# SolarCharge.net
KiCad netlist of a schematic drawn in EAGLE
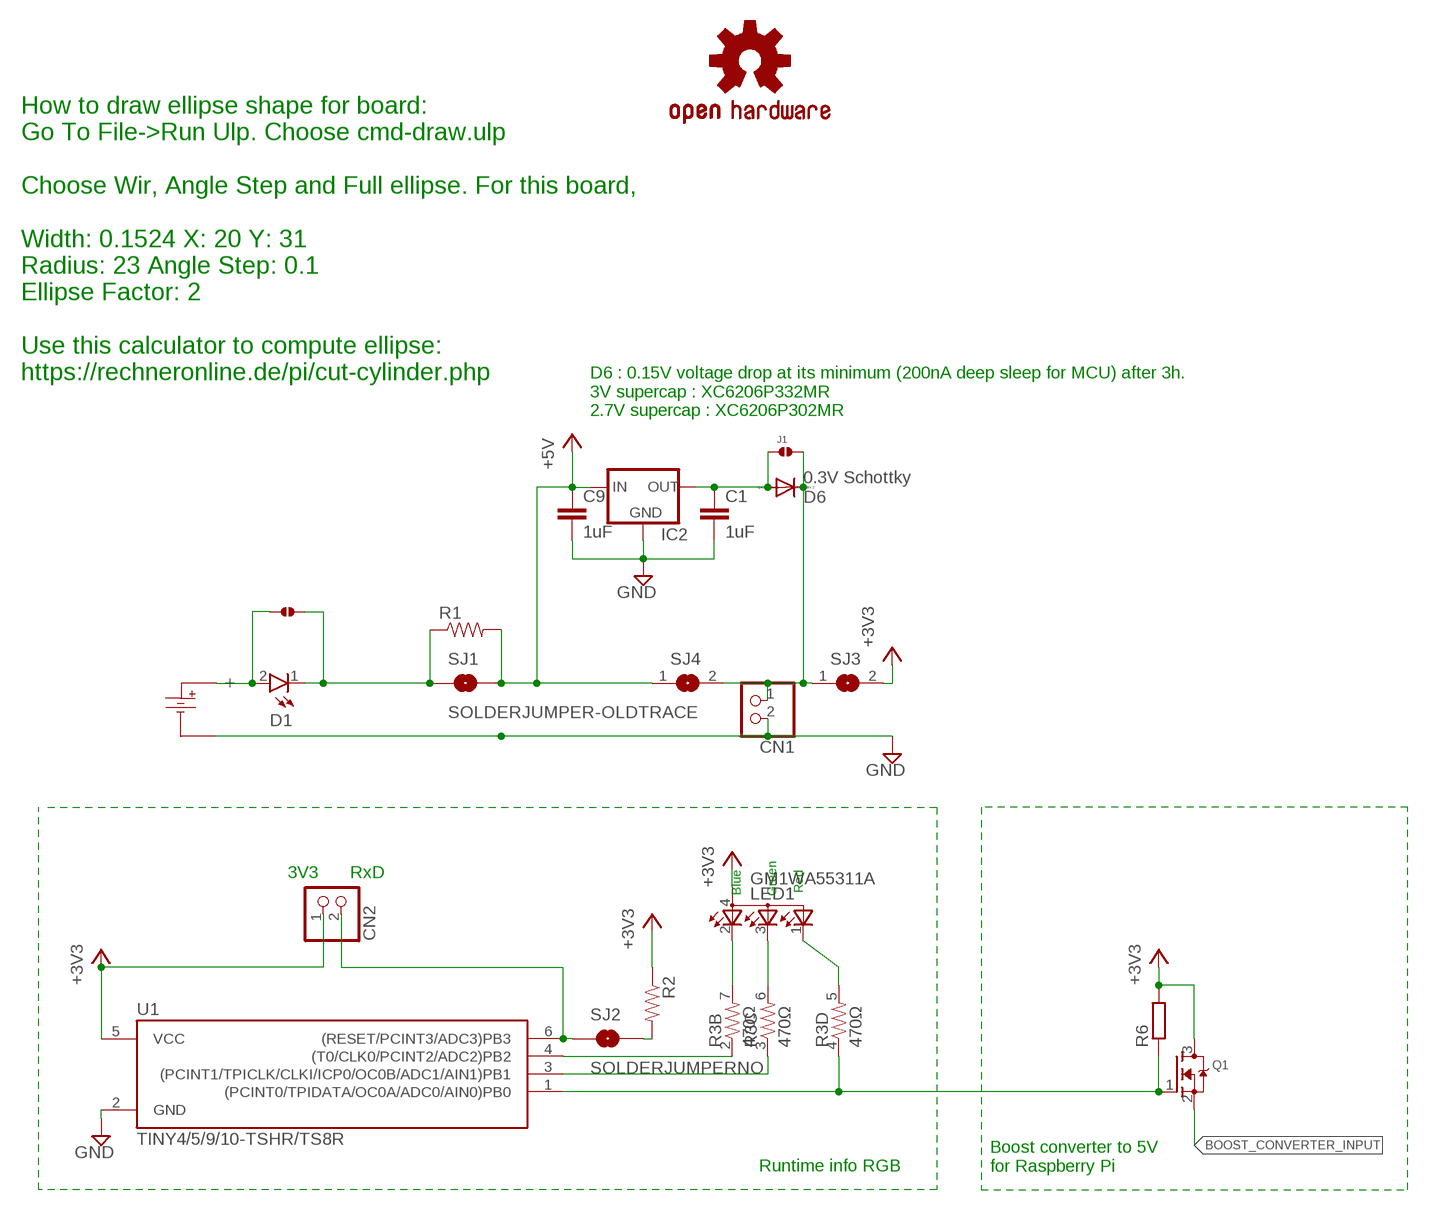
[diagram p0: schematic, sheet 1]

(export (version "E")
  (design (tool "Eeschema 10.0.6"))
  (components
    (comp (ref "C1")
      (value "1uF")
      (footprint "eagle-import:C0603")
      (libsource (lib "eagle-import") (part "C-EUC0603"))
    )
    (comp (ref "C9")
      (value "1uF")
      (footprint "eagle-import:C0603")
      (libsource (lib "eagle-import") (part "C-EUC0603"))
    )
    (comp (ref "CN1")
      (value "JST_2PIN-SMT-RA")
      (footprint "eagle-import:JST-PH-2-SMT-RA")
      (libsource (lib "eagle-import") (part "JST_2PIN-SMT-RA"))
    )
    (comp (ref "CN2")
      (value "JST_2PIN-SMT-RA")
      (footprint "eagle-import:JST-PH-2-SMT-RA")
      (libsource (lib "eagle-import") (part "JST_2PIN-SMT-RA"))
    )
    (comp (ref "D1")
      (value "WL-SWTP3014")
      (footprint "eagle-import:WL-SWTP_3014")
      (libsource (lib "eagle-import") (part "WL-SWTP3014"))
    )
    (comp (ref "D6")
      (value "0.3V Schottky")
      (footprint "eagle-import:SOD523")
      (libsource (lib "eagle-import") (part "DIODE-SOD523"))
    )
    (comp (ref "IC2")
      (value "MCP1700TT")
      (footprint "eagle-import:SOT-23")
      (libsource (lib "eagle-import") (part "MCP1700TT"))
    )
    (comp (ref "J1")
      (value "SOLDERJUMPER.2.MED")
      (footprint "eagle-import:2.MED")
      (libsource (lib "eagle-import") (part "SOLDERJUMPER.2.MED"))
    )
    (comp (ref "J3")
      (value "SOLDERJUMPER.2.XL")
      (footprint "eagle-import:2.XL")
      (libsource (lib "eagle-import") (part "SOLDERJUMPER.2.XL"))
    )
    (comp (ref "LED1")
      (value "GM1WA55311A")
      (footprint "eagle-import:GM1WA55311A")
      (libsource (lib "eagle-import") (part "GM1WA55311A"))
    )
    (comp (ref "LOGO1")
      (value "OSHW-LOGOM")
      (footprint "eagle-import:OSHW-LOGO-M")
      (libsource (lib "eagle-import") (part "OSHW-LOGOM"))
    )
    (comp (ref "Q1")
      (value "MOSFET-NREFLOW")
      (footprint "eagle-import:SOT23")
      (libsource (lib "eagle-import") (part "MOSFET-NREFLOW"))
    )
    (comp (ref "R1")
      (value "RESISTOR0603-RES")
      (footprint "eagle-import:0603-RES")
      (libsource (lib "eagle-import") (part "RESISTOR0603-RES"))
    )
    (comp (ref "R2")
      (value "RESISTOR0603-RES")
      (footprint "eagle-import:0603-RES")
      (libsource (lib "eagle-import") (part "RESISTOR0603-RES"))
    )
    (comp (ref "R3")
      (value "470Ω")
      (footprint "eagle-import:0603-ARV")
      (libsource (lib "eagle-import") (part "RESISTOR-ARRAY0603-ARV"))
    )
    (comp (ref "R6")
      (value "R-EU_R0603")
      (footprint "eagle-import:R0603")
      (libsource (lib "eagle-import") (part "R-EU_R0603"))
    )
    (comp (ref "SJ1")
      (value "SOLDERJUMPER-OLDTRACE")
      (footprint "eagle-import:SJ_2S-TRACE")
      (libsource (lib "eagle-import") (part "SOLDERJUMPER-OLDTRACE"))
    )
    (comp (ref "SJ2")
      (value "SOLDERJUMPERNO")
      (footprint "eagle-import:SJ_2S-NO")
      (libsource (lib "eagle-import") (part "SOLDERJUMPERNO"))
    )
    (comp (ref "SJ3") (value "SJ") (footprint "eagle-import:SJ") (libsource (lib "eagle-import") (part "SJ")))
    (comp (ref "SJ4") (value "SJ") (footprint "eagle-import:SJ") (libsource (lib "eagle-import") (part "SJ")))
    (comp (ref "U$1")
      (value "SOLAR_CELL_53_30")
      (footprint "eagle-import:SOLAR_CELL_53_30")
      (libsource (lib "eagle-import") (part "SOLAR_CELL_53_30"))
    )
    (comp (ref "U1")
      (value "TINY4/5/9/10-TSHR/TS8R")
      (footprint "eagle-import:SOT-23-6")
      (libsource (lib "eagle-import") (part "TINY4/5/9/10-TSHR/TS8R"))
    )
  )
  (nets
    (net (code "1") (name "+3V3") (class "Default")
      (node (ref "CN2") (pin "1") (pinfunction "2_1") (pintype "passive"))
      (node (ref "LED1") (pin "4") (pinfunction "A_4") (pintype "passive"))
      (node (ref "Q1") (pin "3") (pinfunction "D_3") (pintype "bidirectional"))
      (node (ref "R2") (pin "1") (pinfunction "1_1") (pintype "passive"))
      (node (ref "R6") (pin "2") (pinfunction "2_2") (pintype "passive"))
      (node (ref "SJ3") (pin "2") (pinfunction "2_2") (pintype "passive"))
      (node (ref "U1") (pin "5") (pinfunction "VCC_5") (pintype "bidirectional"))
    )
    (net (code "2") (name "+5V") (class "Default")
      (node (ref "C9") (pin "1") (pinfunction "1_1") (pintype "passive"))
      (node (ref "IC2") (pin "3") (pinfunction "IN_3") (pintype "input"))
      (node (ref "R1") (pin "2") (pinfunction "2_2") (pintype "passive"))
      (node (ref "SJ1") (pin "2") (pinfunction "2_2") (pintype "passive"))
      (node (ref "SJ4") (pin "1") (pinfunction "1_1") (pintype "passive"))
    )
    (net (code "3") (name "BOOST_CONVERTER_INPUT") (class "Default")
      (node (ref "Q1") (pin "2") (pinfunction "S_2") (pintype "bidirectional"))
    )
    (net (code "4") (name "GND") (class "Default")
      (node (ref "C1") (pin "2") (pinfunction "2_2") (pintype "passive"))
      (node (ref "C9") (pin "2") (pinfunction "2_2") (pintype "passive"))
      (node (ref "CN1") (pin "2") (pinfunction "1_2") (pintype "passive"))
      (node (ref "IC2") (pin "1") (pinfunction "GND_1") (pintype "input"))
      (node (ref "U$1") (pin "P$2") (pinfunction "P$2_P$2") (pintype "bidirectional"))
      (node (ref "U1") (pin "2") (pinfunction "GND_2") (pintype "bidirectional"))
    )
    (net (code "5") (name "Net-(CN1-2)") (class "Default")
      (node (ref "CN1") (pin "1") (pinfunction "2_1") (pintype "passive"))
      (node (ref "D6") (pin "C") (pinfunction "C_C") (pintype "passive"))
      (node (ref "J1") (pin "2") (pinfunction "2_2") (pintype "bidirectional"))
      (node (ref "SJ3") (pin "1") (pinfunction "1_1") (pintype "passive"))
      (node (ref "SJ4") (pin "2") (pinfunction "2_2") (pintype "passive"))
    )
    (net (code "6") (name "Net-(CN2-1)") (class "Default")
      (node (ref "CN2") (pin "2") (pinfunction "1_2") (pintype "passive"))
      (node (ref "SJ2") (pin "1") (pinfunction "1_1") (pintype "passive"))
      (node (ref "U1") (pin "6") (pinfunction "(RESET/PCINT3/ADC3)PB3_6") (pintype "bidirectional"))
    )
    (net (code "7") (name "Net-(D1-Pad1)") (class "Default")
      (node (ref "D1") (pin "1") (pinfunction "1_1") (pintype "bidirectional"))
      (node (ref "J3") (pin "2") (pinfunction "2_2") (pintype "bidirectional"))
      (node (ref "R1") (pin "1") (pinfunction "1_1") (pintype "passive"))
      (node (ref "SJ1") (pin "1") (pinfunction "1_1") (pintype "passive"))
    )
    (net (code "8") (name "Net-(D1-Pad2)") (class "Default")
      (node (ref "D1") (pin "2") (pinfunction "2_2") (pintype "bidirectional"))
      (node (ref "J3") (pin "1") (pinfunction "1_1") (pintype "bidirectional"))
      (node (ref "U$1") (pin "P$1") (pinfunction "P$1_P$1") (pintype "bidirectional"))
    )
    (net (code "9") (name "Net-(IC2-OUT)") (class "Default")
      (node (ref "C1") (pin "1") (pinfunction "1_1") (pintype "passive"))
      (node (ref "D6") (pin "A") (pinfunction "A_A") (pintype "passive"))
      (node (ref "IC2") (pin "2") (pinfunction "OUT_2") (pintype "passive"))
      (node (ref "J1") (pin "1") (pinfunction "1_1") (pintype "bidirectional"))
    )
    (net (code "10") (name "Net-(LED1-CBLUE)") (class "Default")
      (node (ref "LED1") (pin "3") (pinfunction "CBLUE_3") (pintype "passive"))
      (node (ref "R3") (pin "6") (pinfunction "2_6") (pintype "passive"))
    )
    (net (code "11") (name "Net-(LED1-CGREEN)") (class "Default")
      (node (ref "LED1") (pin "1") (pinfunction "CGREEN_1") (pintype "passive"))
      (node (ref "R3") (pin "5") (pinfunction "2_5") (pintype "passive"))
    )
    (net (code "12") (name "Net-(LED1-CRED)") (class "Default")
      (node (ref "LED1") (pin "2") (pinfunction "CRED_2") (pintype "passive"))
      (node (ref "R3") (pin "7") (pinfunction "2_7") (pintype "passive"))
    )
    (net (code "13") (name "Net-(Q1-G)") (class "Default")
      (node (ref "Q1") (pin "1") (pinfunction "G_1") (pintype "bidirectional"))
      (node (ref "R3") (pin "4") (pinfunction "1_4") (pintype "passive"))
      (node (ref "R6") (pin "1") (pinfunction "1_1") (pintype "passive"))
      (node (ref "U1") (pin "1") (pinfunction "(PCINT0/TPIDATA/OC0A/ADC0/AIN0)PB0_1") (pintype "bidirectional"))
    )
    (net (code "14") (name "Net-(R2-Pad2)") (class "Default")
      (node (ref "R2") (pin "2") (pinfunction "2_2") (pintype "passive"))
      (node (ref "SJ2") (pin "2") (pinfunction "2_2") (pintype "passive"))
    )
    (net (code "15") (name "Net-(R3B-1)") (class "Default")
      (node (ref "R3") (pin "2") (pinfunction "1_2") (pintype "passive"))
      (node (ref "U1") (pin "4") (pinfunction "(T0/CLK0/PCINT2/ADC2)PB2_4") (pintype "bidirectional"))
    )
    (net (code "16") (name "Net-(R3C-1)") (class "Default")
      (node (ref "R3") (pin "3") (pinfunction "1_3") (pintype "passive"))
      (node (ref "U1") (pin "3") (pinfunction "(PCINT1/TPICLK/CLKI/ICP0/OC0B/ADC1/AIN1)PB1_3") (pintype "bidirectional"))
    )
  )
)
